# TPS61022_Breakout.net
KiCad netlist of a schematic drawn in EAGLE
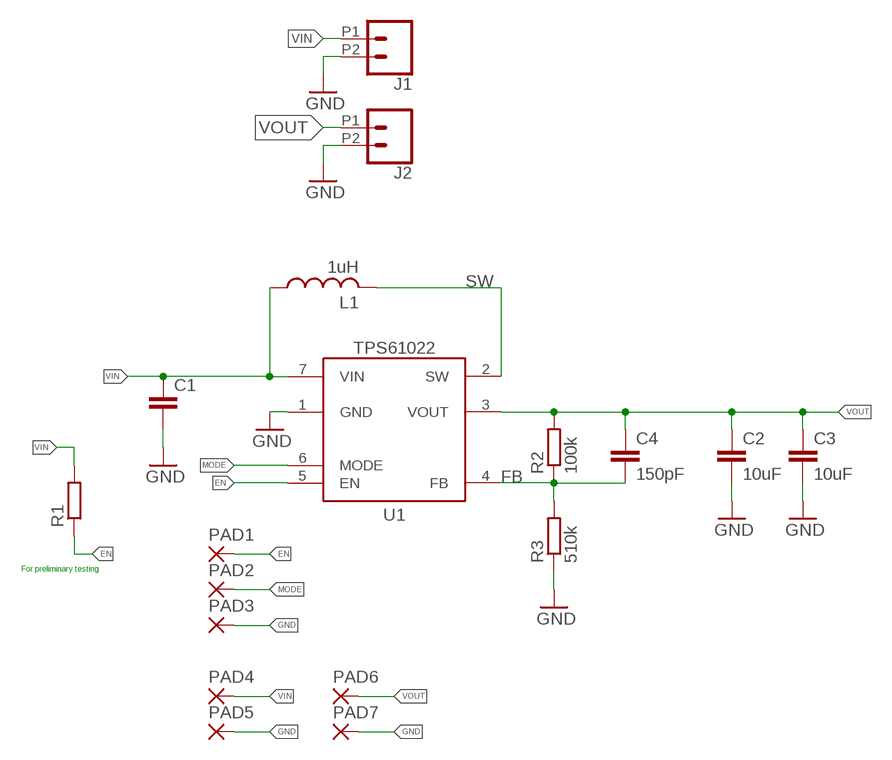
[diagram p0: schematic, sheet 1]

(export (version "E")
  (design (tool "Eeschema 10.0.6"))
  (components
    (comp (ref "C1")
      (value "C-EUC0805")
      (footprint "eagle-import:C0805")
      (libsource (lib "eagle-import") (part "C-EUC0805"))
    )
    (comp (ref "C2")
      (value "10uF")
      (footprint "eagle-import:C0805")
      (fields (field (name "MF") "Murata") (field (name "MPN") "GRM21BR61C106KE15K"))
      (libsource (lib "eagle-import") (part "C-EUC080510UF"))
    )
    (comp (ref "C3")
      (value "10uF")
      (footprint "eagle-import:C0805")
      (fields (field (name "MF") "Murata") (field (name "MPN") "GRM21BR61C106KE15K"))
      (libsource (lib "eagle-import") (part "C-EUC080510UF"))
    )
    (comp (ref "C4")
      (value "150pF")
      (footprint "eagle-import:C0603")
      (libsource (lib "eagle-import") (part "C-EUC0603"))
    )
    (comp (ref "J1")
      (value "CONN_022.54_SCREW_ROUND")
      (footprint "eagle-import:1X02_2.54_SCREWTERM_ROUND")
      (fields (field (name "MF") "OnShore") (field (name "MPN") "OSTVN02A150"))
      (libsource (lib "eagle-import") (part "CONN_022.54_SCREW_ROUND"))
    )
    (comp (ref "J2")
      (value "CONN_022.54_SCREW_ROUND")
      (footprint "eagle-import:1X02_2.54_SCREWTERM_ROUND")
      (fields (field (name "MF") "OnShore") (field (name "MPN") "OSTVN02A150"))
      (libsource (lib "eagle-import") (part "CONN_022.54_SCREW_ROUND"))
    )
    (comp (ref "L1")
      (value "1uH")
      (footprint "eagle-import:WE-HCI(5040)")
      (libsource (lib "eagle-import") (part "INDUCTOR_HCI_5040"))
    )
    (comp (ref "PAD1")
      (value "SMD2")
      (footprint "eagle-import:SMD1,27-2,54")
      (fields (field (name "MPN") "DNP"))
      (libsource (lib "eagle-import") (part "SMD2"))
    )
    (comp (ref "PAD2")
      (value "SMD2")
      (footprint "eagle-import:SMD1,27-2,54")
      (fields (field (name "MPN") "DNP"))
      (libsource (lib "eagle-import") (part "SMD2"))
    )
    (comp (ref "PAD3")
      (value "SMD2")
      (footprint "eagle-import:SMD1,27-2,54")
      (fields (field (name "MPN") "DNP"))
      (libsource (lib "eagle-import") (part "SMD2"))
    )
    (comp (ref "PAD4")
      (value "SMD5")
      (footprint "eagle-import:SMD2,54-5,08")
      (libsource (lib "eagle-import") (part "SMD5"))
    )
    (comp (ref "PAD5")
      (value "SMD5")
      (footprint "eagle-import:SMD2,54-5,08")
      (libsource (lib "eagle-import") (part "SMD5"))
    )
    (comp (ref "PAD6")
      (value "SMD5")
      (footprint "eagle-import:SMD2,54-5,08")
      (libsource (lib "eagle-import") (part "SMD5"))
    )
    (comp (ref "PAD7")
      (value "SMD5")
      (footprint "eagle-import:SMD2,54-5,08")
      (libsource (lib "eagle-import") (part "SMD5"))
    )
    (comp (ref "R1")
      (value "R-EU_100KR0603")
      (footprint "eagle-import:R0603")
      (fields
        (field (name "MF") "Yageo")
        (field (name "MPN") "RC0603FR-07100KL")
        (field (name "VALUE_PART") "100k")
      )
      (libsource (lib "eagle-import") (part "R-EU_R0603100K"))
    )
    (comp (ref "R2")
      (value "100k")
      (footprint "eagle-import:R0603")
      (fields (field (name "MF") "Yageo") (field (name "MPN") "RC0603FR-07100KL"))
      (libsource (lib "eagle-import") (part "R-EU_R0603100K"))
    )
    (comp (ref "R3")
      (value "510k")
      (footprint "eagle-import:R0603")
      (fields (field (name "MF") "Yageo"))
      (libsource (lib "eagle-import") (part "R-EU_R0603"))
    )
    (comp (ref "U1")
      (value "TPS61022")
      (footprint "eagle-import:RWU0007A")
      (fields (field (name "MF") "TI") (field (name "MPN") "TPS61022RWUT"))
      (libsource (lib "eagle-import") (part "TPS61022"))
    )
  )
  (nets
    (net (code "1") (name "/FB") (class "Default")
      (node (ref "C4") (pin "2") (pinfunction "2_2") (pintype "passive"))
      (node (ref "R2") (pin "1") (pinfunction "1_1") (pintype "passive"))
      (node (ref "R3") (pin "2") (pinfunction "2_2") (pintype "passive"))
      (node (ref "U1") (pin "4") (pinfunction "FB_4") (pintype "input"))
    )
    (net (code "2") (name "/SW") (class "Default")
      (node (ref "L1") (pin "P$2") (pinfunction "2_P$2") (pintype "passive"))
      (node (ref "U1") (pin "2") (pinfunction "SW_2") (pintype "power_in"))
    )
    (net (code "3") (name "EN") (class "Default")
      (node (ref "PAD1") (pin "1") (pinfunction "P_1") (pintype "passive"))
      (node (ref "R1") (pin "1") (pinfunction "1_1") (pintype "passive"))
      (node (ref "U1") (pin "5") (pinfunction "EN_5") (pintype "input"))
    )
    (net (code "4") (name "GND") (class "Default")
      (node (ref "C1") (pin "2") (pinfunction "2_2") (pintype "passive"))
      (node (ref "C2") (pin "2") (pinfunction "2_2") (pintype "passive"))
      (node (ref "C3") (pin "2") (pinfunction "2_2") (pintype "passive"))
      (node (ref "J1") (pin "P2") (pinfunction "2_P2") (pintype "passive"))
      (node (ref "J2") (pin "P2") (pinfunction "2_P2") (pintype "passive"))
      (node (ref "PAD3") (pin "1") (pinfunction "P_1") (pintype "passive"))
      (node (ref "PAD5") (pin "1") (pinfunction "P_1") (pintype "passive"))
      (node (ref "PAD7") (pin "1") (pinfunction "P_1") (pintype "passive"))
      (node (ref "R3") (pin "1") (pinfunction "1_1") (pintype "passive"))
      (node (ref "U1") (pin "1") (pinfunction "GND_1") (pintype "power_in"))
    )
    (net (code "5") (name "MODE") (class "Default")
      (node (ref "PAD2") (pin "1") (pinfunction "P_1") (pintype "passive"))
      (node (ref "U1") (pin "6") (pinfunction "MODE_6") (pintype "input"))
    )
    (net (code "6") (name "VIN") (class "Default")
      (node (ref "C1") (pin "1") (pinfunction "1_1") (pintype "passive"))
      (node (ref "J1") (pin "P1") (pinfunction "1_P1") (pintype "passive"))
      (node (ref "L1") (pin "P$1") (pinfunction "1_P$1") (pintype "passive"))
      (node (ref "PAD4") (pin "1") (pinfunction "P_1") (pintype "passive"))
      (node (ref "R1") (pin "2") (pinfunction "2_2") (pintype "passive"))
      (node (ref "U1") (pin "7") (pinfunction "VIN_7") (pintype "power_in"))
    )
    (net (code "7") (name "VOUT") (class "Default")
      (node (ref "C2") (pin "1") (pinfunction "1_1") (pintype "passive"))
      (node (ref "C3") (pin "1") (pinfunction "1_1") (pintype "passive"))
      (node (ref "C4") (pin "1") (pinfunction "1_1") (pintype "passive"))
      (node (ref "J2") (pin "P1") (pinfunction "1_P1") (pintype "passive"))
      (node (ref "PAD6") (pin "1") (pinfunction "P_1") (pintype "passive"))
      (node (ref "R2") (pin "2") (pinfunction "2_2") (pintype "passive"))
      (node (ref "U1") (pin "3") (pinfunction "VOUT_3") (pintype "power_in"))
    )
  )
)
